# level_converter.net
KiCad netlist of a schematic drawn in Altium Designer
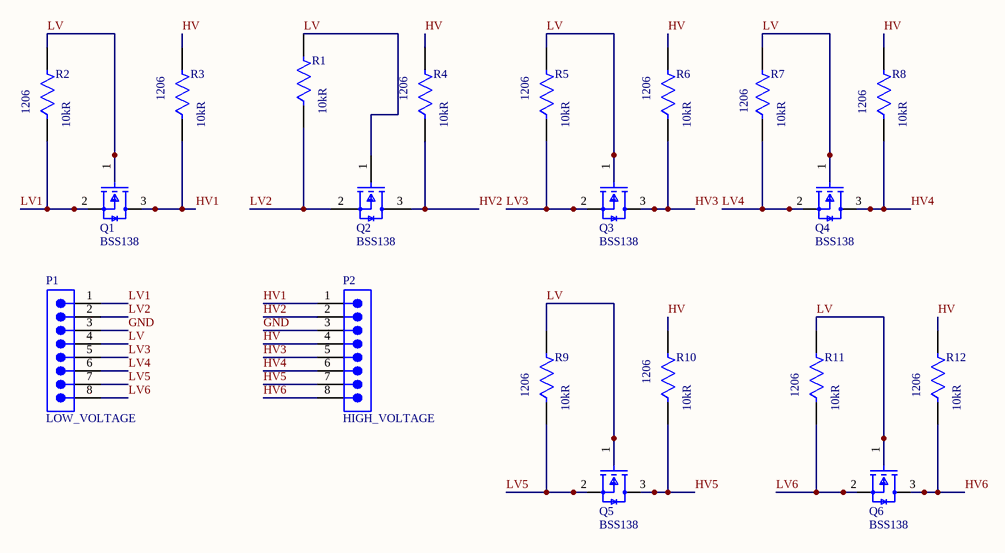
[diagram p0: level_converter.SchDoc]

(export (version "E")
  (design (tool "Eeschema 10.0.6"))
  (components
    (comp (ref "P1")
      (value "LOW_VOLTAGE")
      (footprint "66200811122")
      (libsource (lib "Altium Content Vault") (part "Header_Male_1R_08P"))
    )
    (comp (ref "P2")
      (value "HIGH_VOLTAGE")
      (footprint "66200811122")
      (libsource (lib "Altium Content Vault") (part "Header_Male_1R_08P"))
    )
    (comp (ref "Q1")
      (value "BSS138")
      (footprint "FP-318-08-IPC_B")
      (description "MOSFET N-CH 50V 220MA SOT-23")
      (libsource (lib "Altium Content Vault") (part "3b9c635fedb024a5347a57b145af9cc"))
    )
    (comp (ref "Q2")
      (value "BSS138")
      (footprint "FP-318-08-IPC_B")
      (description "MOSFET N-CH 50V 220MA SOT-23")
      (libsource (lib "Altium Content Vault") (part "3b9c635fedb024a5347a57b145af9cc"))
    )
    (comp (ref "Q3")
      (value "BSS138")
      (footprint "FP-318-08-IPC_B")
      (description "MOSFET N-CH 50V 220MA SOT-23")
      (libsource (lib "Altium Content Vault") (part "3b9c635fedb024a5347a57b145af9cc"))
    )
    (comp (ref "Q4")
      (value "BSS138")
      (footprint "FP-318-08-IPC_B")
      (description "MOSFET N-CH 50V 220MA SOT-23")
      (libsource (lib "Altium Content Vault") (part "3b9c635fedb024a5347a57b145af9cc"))
    )
    (comp (ref "Q5")
      (value "BSS138")
      (footprint "FP-318-08-IPC_B")
      (description "MOSFET N-CH 50V 220MA SOT-23")
      (libsource (lib "Altium Content Vault") (part "3b9c635fedb024a5347a57b145af9cc"))
    )
    (comp (ref "Q6")
      (value "BSS138")
      (footprint "FP-318-08-IPC_B")
      (description "MOSFET N-CH 50V 220MA SOT-23")
      (libsource (lib "Altium Content Vault") (part "3b9c635fedb024a5347a57b145af9cc"))
    )
    (comp (ref "R1")
      (value "CRCW120610K0FKEA")
      (footprint "FP-CRCW1206-e3-IPC_C")
      (description "RES Thick Film, 10kΩ, 1%, 0.25W, 100ppm/°C, 1206")
      (fields (field (name "TOLERANCE") "1%") (field (name "RESISTANCE") "10kR"))
      (libsource (lib "Altium Content Vault") (part "1029c3af85768c4190bb7ad29bc67b5"))
    )
    (comp (ref "R2")
      (value "CRCW120610K0FKEA")
      (footprint "FP-CRCW1206-e3-IPC_C")
      (description "RES Thick Film, 10kΩ, 1%, 0.25W, 100ppm/°C, 1206")
      (fields
        (field (name "TOLERANCE") "1%")
        (field (name "RESISTANCE") "10kR")
        (field (name "CASE/PACKAGE") "1206")
      )
      (libsource (lib "Altium Content Vault") (part "1029c3af85768c4190bb7ad29bc67b5"))
    )
    (comp (ref "R3")
      (value "CRCW120610K0FKEA")
      (footprint "FP-CRCW1206-e3-IPC_C")
      (description "RES Thick Film, 10kΩ, 1%, 0.25W, 100ppm/°C, 1206")
      (fields
        (field (name "TOLERANCE") "1%")
        (field (name "RESISTANCE") "10kR")
        (field (name "CASE CODE (IMPERIAL)") "1206")
      )
      (libsource (lib "Altium Content Vault") (part "1029c3af85768c4190bb7ad29bc67b5"))
    )
    (comp (ref "R4")
      (value "CRCW120610K0FKEA")
      (footprint "FP-CRCW1206-e3-IPC_C")
      (description "RES Thick Film, 10kΩ, 1%, 0.25W, 100ppm/°C, 1206")
      (fields
        (field (name "TOLERANCE") "1%")
        (field (name "RESISTANCE") "10kR")
        (field (name "CASE/PACKAGE") "1206")
      )
      (libsource (lib "Altium Content Vault") (part "1029c3af85768c4190bb7ad29bc67b5"))
    )
    (comp (ref "R5")
      (value "CRCW120610K0FKEA")
      (footprint "FP-CRCW1206-e3-IPC_C")
      (description "RES Thick Film, 10kΩ, 1%, 0.25W, 100ppm/°C, 1206")
      (fields
        (field (name "TOLERANCE") "1%")
        (field (name "RESISTANCE") "10kR")
        (field (name "CASE/PACKAGE") "1206")
      )
      (libsource (lib "Altium Content Vault") (part "1029c3af85768c4190bb7ad29bc67b5"))
    )
    (comp (ref "R6")
      (value "CRCW120610K0FKEA")
      (footprint "FP-CRCW1206-e3-IPC_C")
      (description "RES Thick Film, 10kΩ, 1%, 0.25W, 100ppm/°C, 1206")
      (fields
        (field (name "TOLERANCE") "1%")
        (field (name "RESISTANCE") "10kR")
        (field (name "CASE/PACKAGE") "1206")
      )
      (libsource (lib "Altium Content Vault") (part "1029c3af85768c4190bb7ad29bc67b5"))
    )
    (comp (ref "R7")
      (value "CRCW120610K0FKEA")
      (footprint "FP-CRCW1206-e3-IPC_C")
      (description "RES Thick Film, 10kΩ, 1%, 0.25W, 100ppm/°C, 1206")
      (fields
        (field (name "TOLERANCE") "1%")
        (field (name "RESISTANCE") "10kR")
        (field (name "CASE/PACKAGE") "1206")
      )
      (libsource (lib "Altium Content Vault") (part "1029c3af85768c4190bb7ad29bc67b5"))
    )
    (comp (ref "R8")
      (value "CRCW120610K0FKEA")
      (footprint "FP-CRCW1206-e3-IPC_C")
      (description "RES Thick Film, 10kΩ, 1%, 0.25W, 100ppm/°C, 1206")
      (fields
        (field (name "TOLERANCE") "1%")
        (field (name "RESISTANCE") "10kR")
        (field (name "CASE/PACKAGE") "1206")
      )
      (libsource (lib "Altium Content Vault") (part "1029c3af85768c4190bb7ad29bc67b5"))
    )
    (comp (ref "R9")
      (value "CRCW120610K0FKEA")
      (footprint "FP-CRCW1206-e3-IPC_C")
      (description "RES Thick Film, 10kΩ, 1%, 0.25W, 100ppm/°C, 1206")
      (fields
        (field (name "TOLERANCE") "1%")
        (field (name "RESISTANCE") "10kR")
        (field (name "CASE/PACKAGE") "1206")
      )
      (libsource (lib "Altium Content Vault") (part "1029c3af85768c4190bb7ad29bc67b5"))
    )
    (comp (ref "R10")
      (value "CRCW120610K0FKEA")
      (footprint "FP-CRCW1206-e3-IPC_C")
      (description "RES Thick Film, 10kΩ, 1%, 0.25W, 100ppm/°C, 1206")
      (fields
        (field (name "TOLERANCE") "1%")
        (field (name "RESISTANCE") "10kR")
        (field (name "CASE/PACKAGE") "1206")
      )
      (libsource (lib "Altium Content Vault") (part "1029c3af85768c4190bb7ad29bc67b5"))
    )
    (comp (ref "R11")
      (value "CRCW120610K0FKEA")
      (footprint "FP-CRCW1206-e3-IPC_C")
      (description "RES Thick Film, 10kΩ, 1%, 0.25W, 100ppm/°C, 1206")
      (fields
        (field (name "TOLERANCE") "1%")
        (field (name "RESISTANCE") "10kR")
        (field (name "CASE/PACKAGE") "1206")
      )
      (libsource (lib "Altium Content Vault") (part "1029c3af85768c4190bb7ad29bc67b5"))
    )
    (comp (ref "R12")
      (value "CRCW120610K0FKEA")
      (footprint "FP-CRCW1206-e3-IPC_C")
      (description "RES Thick Film, 10kΩ, 1%, 0.25W, 100ppm/°C, 1206")
      (fields
        (field (name "TOLERANCE") "1%")
        (field (name "RESISTANCE") "10kR")
        (field (name "CASE/PACKAGE") "1206")
      )
      (libsource (lib "Altium Content Vault") (part "1029c3af85768c4190bb7ad29bc67b5"))
    )
  )
  (nets
    (net (code "1") (name "/GND") (class "Default")
      (node (ref "P1") (pin "3") (pinfunction "3_3") (pintype "passive"))
      (node (ref "P2") (pin "3") (pinfunction "3_3") (pintype "passive"))
    )
    (net (code "2") (name "/HV") (class "Default")
      (node (ref "P2") (pin "4") (pinfunction "4_4") (pintype "passive"))
      (node (ref "R10") (pin "2") (pinfunction "2_2") (pintype "passive"))
      (node (ref "R12") (pin "2") (pinfunction "2_2") (pintype "passive"))
      (node (ref "R3") (pin "2") (pinfunction "2_2") (pintype "passive"))
      (node (ref "R4") (pin "2") (pinfunction "2_2") (pintype "passive"))
      (node (ref "R6") (pin "2") (pinfunction "2_2") (pintype "passive"))
      (node (ref "R8") (pin "2") (pinfunction "2_2") (pintype "passive"))
    )
    (net (code "3") (name "/HV1") (class "Default")
      (node (ref "P2") (pin "1") (pinfunction "1_1") (pintype "passive"))
      (node (ref "Q1") (pin "3") (pinfunction "D_3") (pintype "passive"))
      (node (ref "R3") (pin "1") (pinfunction "1_1") (pintype "passive"))
    )
    (net (code "4") (name "/HV2") (class "Default")
      (node (ref "P2") (pin "2") (pinfunction "2_2") (pintype "passive"))
      (node (ref "Q2") (pin "3") (pinfunction "D_3") (pintype "passive"))
      (node (ref "R4") (pin "1") (pinfunction "1_1") (pintype "passive"))
    )
    (net (code "5") (name "/HV3") (class "Default")
      (node (ref "P2") (pin "5") (pinfunction "5_5") (pintype "passive"))
      (node (ref "Q3") (pin "3") (pinfunction "D_3") (pintype "passive"))
      (node (ref "R6") (pin "1") (pinfunction "1_1") (pintype "passive"))
    )
    (net (code "6") (name "/HV4") (class "Default")
      (node (ref "P2") (pin "6") (pinfunction "6_6") (pintype "passive"))
      (node (ref "Q4") (pin "3") (pinfunction "D_3") (pintype "passive"))
      (node (ref "R8") (pin "1") (pinfunction "1_1") (pintype "passive"))
    )
    (net (code "7") (name "/HV5") (class "Default")
      (node (ref "P2") (pin "7") (pinfunction "7_7") (pintype "passive"))
      (node (ref "Q5") (pin "3") (pinfunction "D_3") (pintype "passive"))
      (node (ref "R10") (pin "1") (pinfunction "1_1") (pintype "passive"))
    )
    (net (code "8") (name "/HV6") (class "Default")
      (node (ref "P2") (pin "8") (pinfunction "8_8") (pintype "passive"))
      (node (ref "Q6") (pin "3") (pinfunction "D_3") (pintype "passive"))
      (node (ref "R12") (pin "1") (pinfunction "1_1") (pintype "passive"))
    )
    (net (code "9") (name "/LV") (class "Default")
      (node (ref "P1") (pin "4") (pinfunction "4_4") (pintype "passive"))
      (node (ref "Q1") (pin "1") (pinfunction "G_1") (pintype "passive"))
      (node (ref "Q2") (pin "1") (pinfunction "G_1") (pintype "passive"))
      (node (ref "Q3") (pin "1") (pinfunction "G_1") (pintype "passive"))
      (node (ref "Q4") (pin "1") (pinfunction "G_1") (pintype "passive"))
      (node (ref "Q5") (pin "1") (pinfunction "G_1") (pintype "passive"))
      (node (ref "Q6") (pin "1") (pinfunction "G_1") (pintype "passive"))
      (node (ref "R1") (pin "2") (pinfunction "2_2") (pintype "passive"))
      (node (ref "R11") (pin "2") (pinfunction "2_2") (pintype "passive"))
      (node (ref "R2") (pin "2") (pinfunction "2_2") (pintype "passive"))
      (node (ref "R5") (pin "2") (pinfunction "2_2") (pintype "passive"))
      (node (ref "R7") (pin "2") (pinfunction "2_2") (pintype "passive"))
      (node (ref "R9") (pin "2") (pinfunction "2_2") (pintype "passive"))
    )
    (net (code "10") (name "/LV1") (class "Default")
      (node (ref "P1") (pin "1") (pinfunction "1_1") (pintype "passive"))
      (node (ref "Q1") (pin "2") (pinfunction "S_2") (pintype "passive"))
      (node (ref "R2") (pin "1") (pinfunction "1_1") (pintype "passive"))
    )
    (net (code "11") (name "/LV2") (class "Default")
      (node (ref "P1") (pin "2") (pinfunction "2_2") (pintype "passive"))
      (node (ref "Q2") (pin "2") (pinfunction "S_2") (pintype "passive"))
      (node (ref "R1") (pin "1") (pinfunction "1_1") (pintype "passive"))
    )
    (net (code "12") (name "/LV3") (class "Default")
      (node (ref "P1") (pin "5") (pinfunction "5_5") (pintype "passive"))
      (node (ref "Q3") (pin "2") (pinfunction "S_2") (pintype "passive"))
      (node (ref "R5") (pin "1") (pinfunction "1_1") (pintype "passive"))
    )
    (net (code "13") (name "/LV4") (class "Default")
      (node (ref "P1") (pin "6") (pinfunction "6_6") (pintype "passive"))
      (node (ref "Q4") (pin "2") (pinfunction "S_2") (pintype "passive"))
      (node (ref "R7") (pin "1") (pinfunction "1_1") (pintype "passive"))
    )
    (net (code "14") (name "/LV5") (class "Default")
      (node (ref "P1") (pin "7") (pinfunction "7_7") (pintype "passive"))
      (node (ref "Q5") (pin "2") (pinfunction "S_2") (pintype "passive"))
      (node (ref "R9") (pin "1") (pinfunction "1_1") (pintype "passive"))
    )
    (net (code "15") (name "/LV6") (class "Default")
      (node (ref "P1") (pin "8") (pinfunction "8_8") (pintype "passive"))
      (node (ref "Q6") (pin "2") (pinfunction "S_2") (pintype "passive"))
      (node (ref "R11") (pin "1") (pinfunction "1_1") (pintype "passive"))
    )
  )
)
